# v1_SCH.net
KiCad netlist of a schematic drawn in EasyEDA Pro
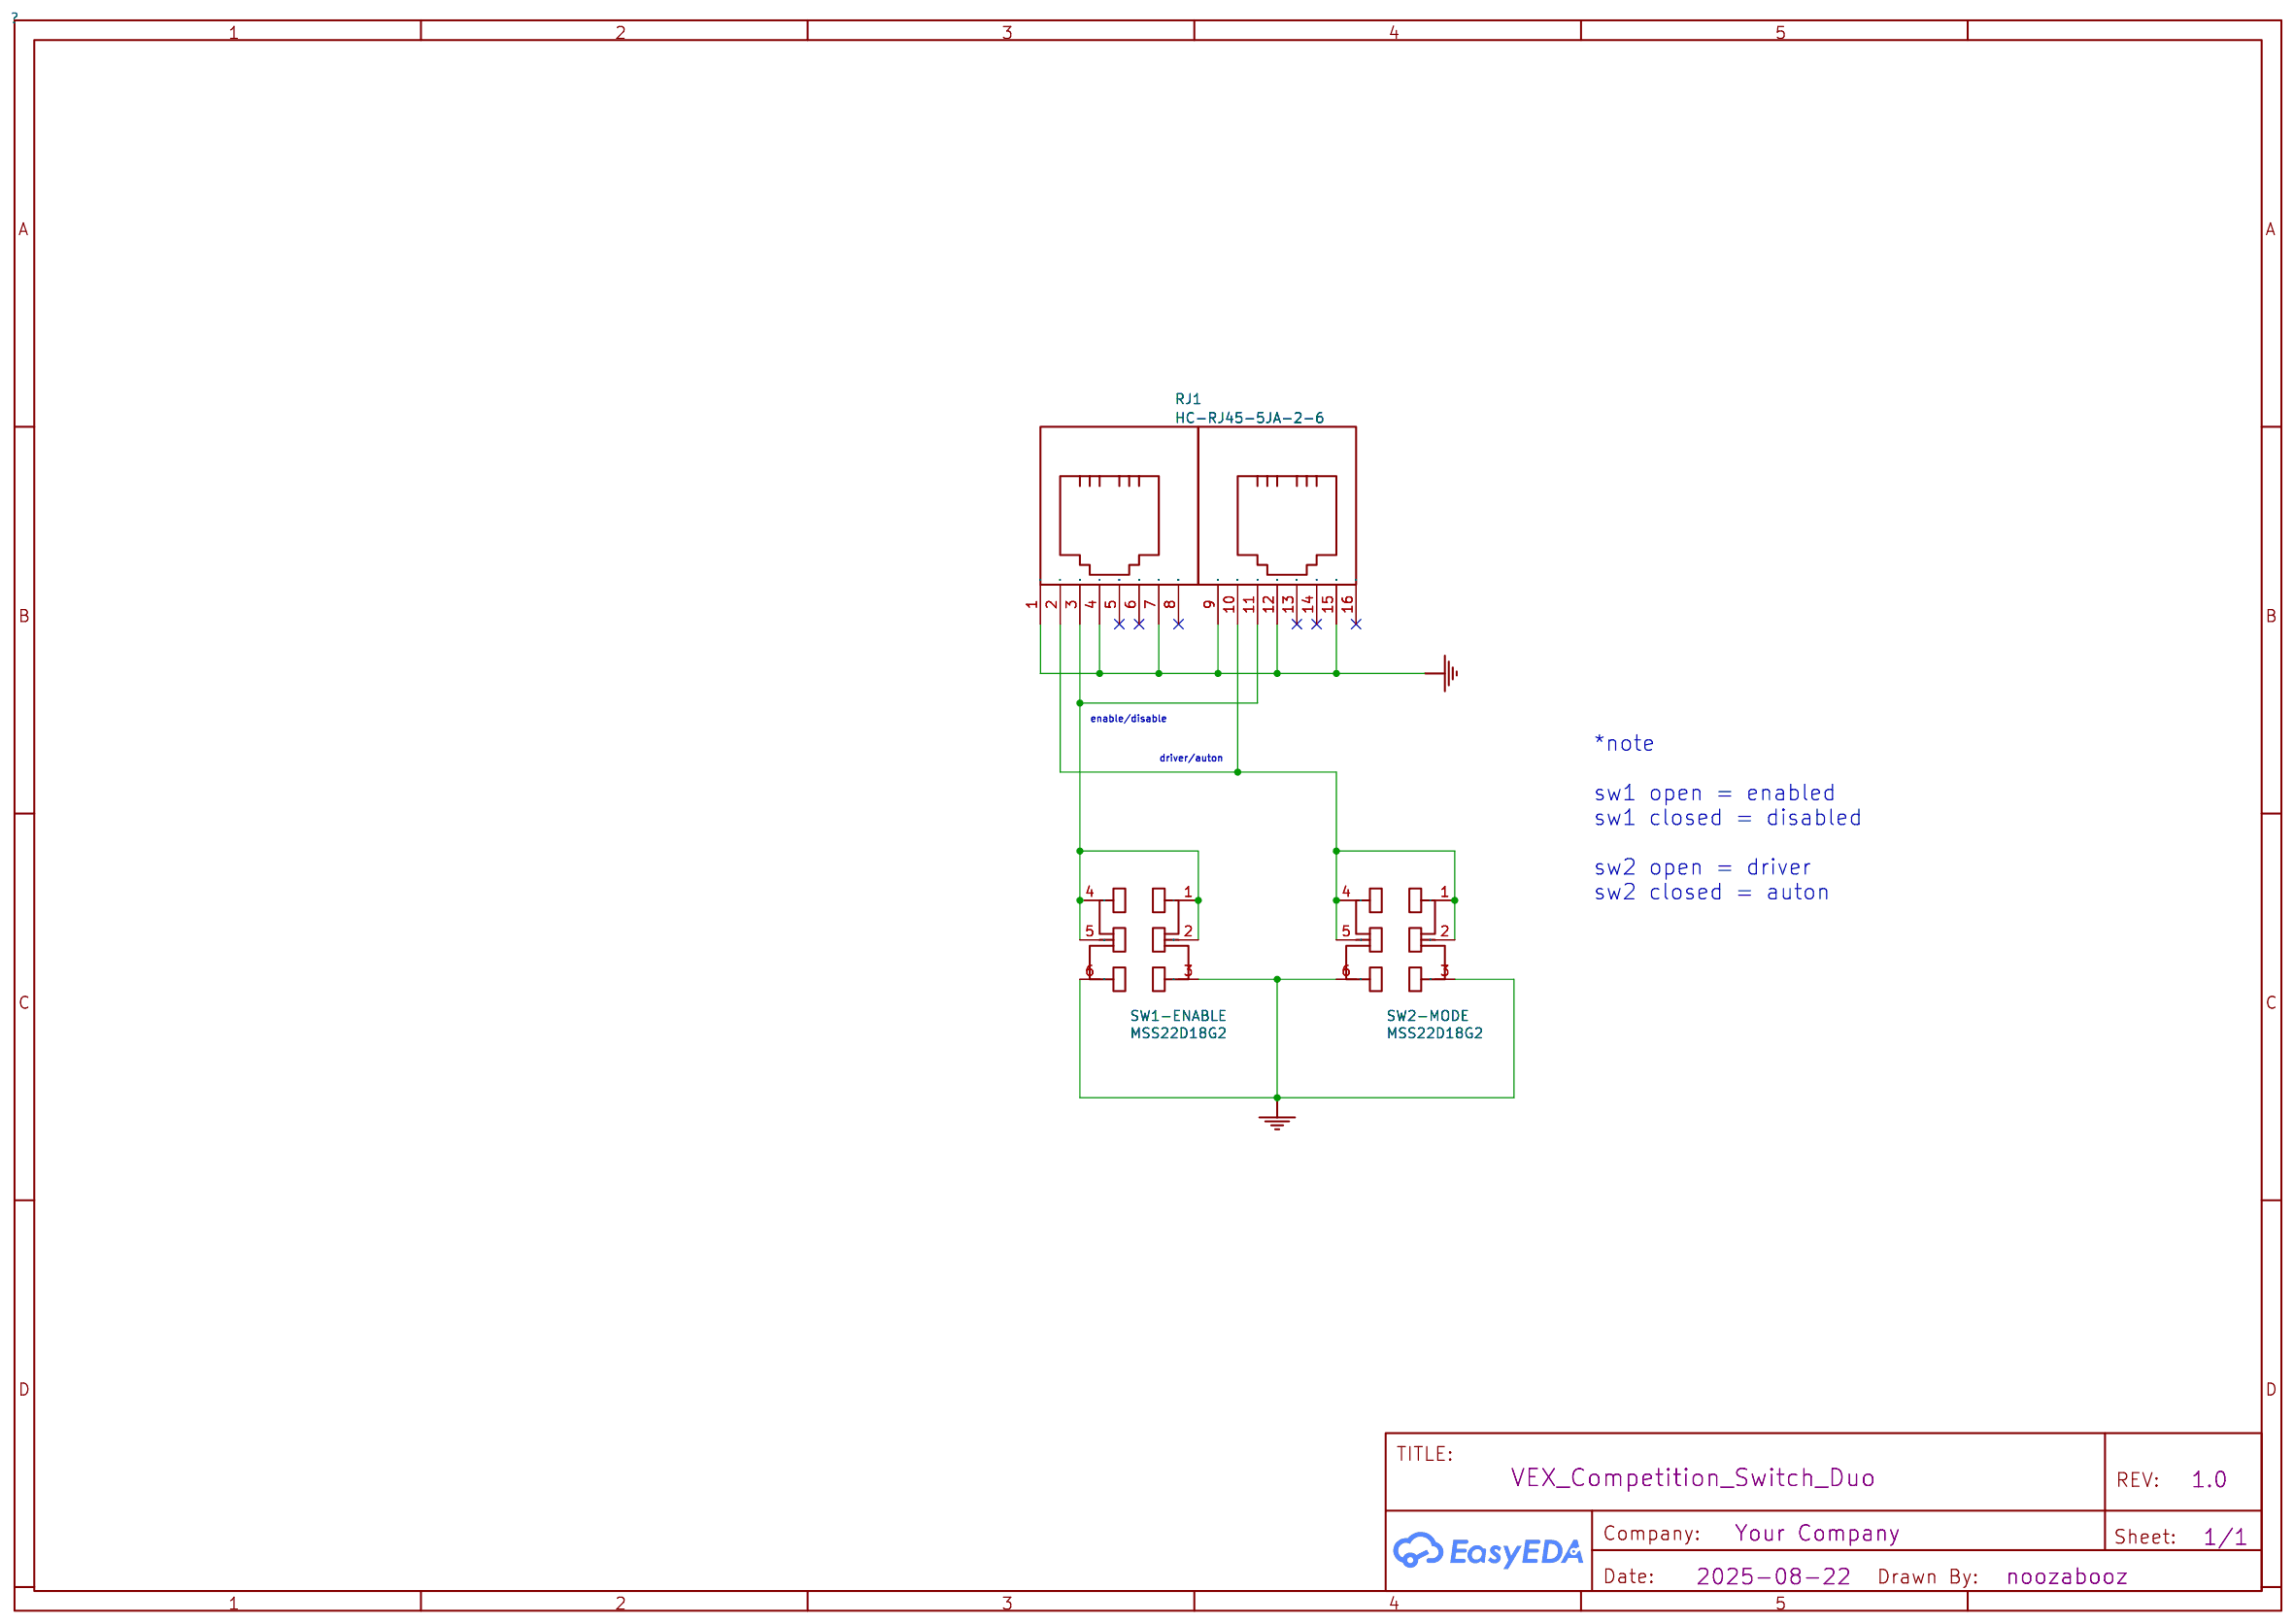
[diagram p0: schematic sheet]

(export (version "E")
  (design (tool "Eeschema 10.0.6"))
  (components
    (comp (ref "RJ1")
      (value "HC-RJ45-5JA-2-6")
      (footprint "easyedapro:RJ45-TH_HC-RJ45-5JA-2-6-S")
      (fields (field (name "Manufacturer") "HCTL(华灿天禄)") (field (name "Contributor") "lcsc"))
      (libsource (lib "easyedapro") (part "HC-RJ45-5JA-2-6"))
    )
    (comp (ref "SW1-ENABLE")
      (value "MSS22D18G2")
      (footprint "easyedapro:SW-TH_MSS22D18GX")
      (fields (field (name "Manufacturer") "SHOU HAN(首韩)") (field (name "Contributor") "LCSC"))
      (libsource (lib "easyedapro") (part "MSS22D18G2"))
    )
    (comp (ref "SW2-MODE")
      (value "MSS22D18G2")
      (footprint "easyedapro:SW-TH_MSS22D18GX")
      (fields (field (name "Manufacturer") "SHOU HAN(首韩)") (field (name "Contributor") "LCSC"))
      (libsource (lib "easyedapro") (part "MSS22D18G2"))
    )
  )
  (nets
    (net (code "1") (name "GND") (class "Default")
      (node (ref "RJ1") (pin "1") (pinfunction "1_1") (pintype "unspecified"))
      (node (ref "RJ1") (pin "12") (pinfunction "12_12") (pintype "unspecified"))
      (node (ref "RJ1") (pin "15") (pinfunction "15_15") (pintype "unspecified"))
      (node (ref "RJ1") (pin "4") (pinfunction "4_4") (pintype "unspecified"))
      (node (ref "RJ1") (pin "7") (pinfunction "7_7") (pintype "unspecified"))
      (node (ref "RJ1") (pin "9") (pinfunction "9_9") (pintype "unspecified"))
      (node (ref "SW1-ENABLE") (pin "3") (pinfunction "3_3") (pintype "unspecified"))
      (node (ref "SW1-ENABLE") (pin "6") (pinfunction "6_6") (pintype "unspecified"))
      (node (ref "SW2-MODE") (pin "3") (pinfunction "3_3") (pintype "unspecified"))
      (node (ref "SW2-MODE") (pin "6") (pinfunction "6_6") (pintype "unspecified"))
    )
    (net (code "2") (name "Net-(RJ1-Pad10)") (class "Default")
      (node (ref "RJ1") (pin "10") (pinfunction "10_10") (pintype "unspecified"))
      (node (ref "RJ1") (pin "2") (pinfunction "2_2") (pintype "unspecified"))
      (node (ref "SW2-MODE") (pin "1") (pinfunction "1_1") (pintype "unspecified"))
      (node (ref "SW2-MODE") (pin "2") (pinfunction "2_2") (pintype "unspecified"))
      (node (ref "SW2-MODE") (pin "4") (pinfunction "4_4") (pintype "unspecified"))
      (node (ref "SW2-MODE") (pin "5") (pinfunction "5_5") (pintype "unspecified"))
    )
    (net (code "3") (name "Net-(RJ1-Pad11)") (class "Default")
      (node (ref "RJ1") (pin "11") (pinfunction "11_11") (pintype "unspecified"))
      (node (ref "RJ1") (pin "3") (pinfunction "3_3") (pintype "unspecified"))
      (node (ref "SW1-ENABLE") (pin "1") (pinfunction "1_1") (pintype "unspecified"))
      (node (ref "SW1-ENABLE") (pin "2") (pinfunction "2_2") (pintype "unspecified"))
      (node (ref "SW1-ENABLE") (pin "4") (pinfunction "4_4") (pintype "unspecified"))
      (node (ref "SW1-ENABLE") (pin "5") (pinfunction "5_5") (pintype "unspecified"))
    )
    (net (code "4") (name "unconnected-(RJ1-Pad5)") (class "Default")
      (node (ref "RJ1") (pin "5") (pinfunction "5_5") (pintype "unspecified+no_connect"))
    )
    (net (code "5") (name "unconnected-(RJ1-Pad6)") (class "Default")
      (node (ref "RJ1") (pin "6") (pinfunction "6_6") (pintype "unspecified+no_connect"))
    )
    (net (code "6") (name "unconnected-(RJ1-Pad8)") (class "Default")
      (node (ref "RJ1") (pin "8") (pinfunction "8_8") (pintype "unspecified+no_connect"))
    )
    (net (code "7") (name "unconnected-(RJ1-Pad13)") (class "Default")
      (node (ref "RJ1") (pin "13") (pinfunction "13_13") (pintype "unspecified+no_connect"))
    )
    (net (code "8") (name "unconnected-(RJ1-Pad14)") (class "Default")
      (node (ref "RJ1") (pin "14") (pinfunction "14_14") (pintype "unspecified+no_connect"))
    )
    (net (code "9") (name "unconnected-(RJ1-Pad16)") (class "Default")
      (node (ref "RJ1") (pin "16") (pinfunction "16_16") (pintype "unspecified+no_connect"))
    )
  )
)
